# brushed_controller.net
KiCad netlist of a schematic drawn in EAGLE
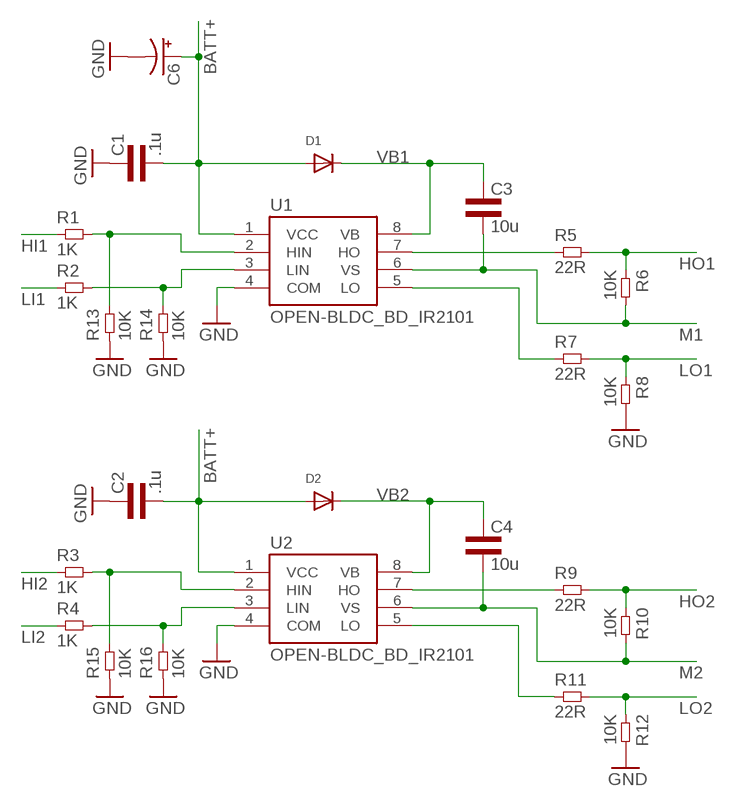
[diagram p0: schematic, sheet 1]
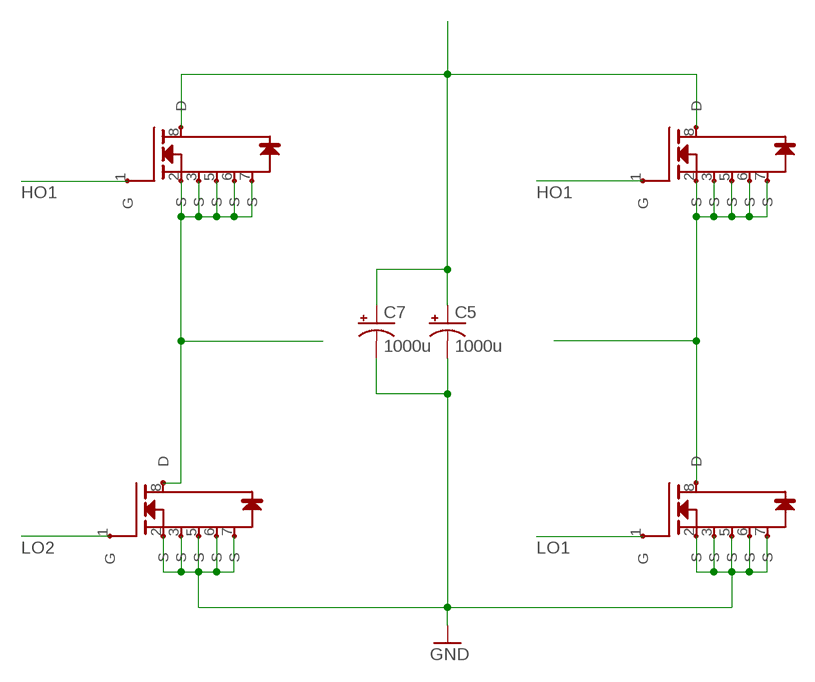
[diagram p1: schematic, sheet 2]

(export (version "E")
  (design (tool "Eeschema 10.0.6"))
  (components
    (comp (ref "C5")
      (value "1000u")
      (footprint "eagle-import:E5-13")
      (libsource (lib "eagle-import") (part "CPOL-USE5-13"))
    )
    (comp (ref "C7")
      (value "1000u")
      (footprint "eagle-import:E5-13")
      (libsource (lib "eagle-import") (part "CPOL-USE5-13"))
    )
    (comp (ref "U$1")
      (value "IR-MOSFETS_IRF3805STRL-7PP")
      (footprint "eagle-import:IR-MOSFETS_D2PAK-7")
      (libsource (lib "eagle-import") (part "IR-MOSFETS_IRF3805STRL-7PP"))
    )
    (comp (ref "U$2")
      (value "IR-MOSFETS_IRF3805STRL-7PP")
      (footprint "eagle-import:IR-MOSFETS_D2PAK-7")
      (libsource (lib "eagle-import") (part "IR-MOSFETS_IRF3805STRL-7PP"))
    )
    (comp (ref "U$3")
      (value "IR-MOSFETS_IRF3805STRL-7PP")
      (footprint "eagle-import:IR-MOSFETS_D2PAK-7")
      (libsource (lib "eagle-import") (part "IR-MOSFETS_IRF3805STRL-7PP"))
    )
    (comp (ref "U$4")
      (value "IR-MOSFETS_IRF3805STRL-7PP")
      (footprint "eagle-import:IR-MOSFETS_D2PAK-7")
      (libsource (lib "eagle-import") (part "IR-MOSFETS_IRF3805STRL-7PP"))
    )
    (comp (ref "C1")
      (value ".1u")
      (footprint "eagle-import:0603L3")
      (libsource (lib "eagle-import") (part "CAP0603L3"))
    )
    (comp (ref "C2")
      (value ".1u")
      (footprint "eagle-import:0603L3")
      (libsource (lib "eagle-import") (part "CAP0603L3"))
    )
    (comp (ref "C3")
      (value "10u")
      (footprint "eagle-import:0805L3")
      (libsource (lib "eagle-import") (part "CAP0805L3"))
    )
    (comp (ref "C4")
      (value "10u")
      (footprint "eagle-import:0805L3")
      (libsource (lib "eagle-import") (part "CAP0805L3"))
    )
    (comp (ref "C6")
      (value "CPOL-USCT7343")
      (footprint "eagle-import:CT7343")
      (libsource (lib "eagle-import") (part "CPOL-USCT7343"))
    )
    (comp (ref "D1")
      (value "DIODESOD-523")
      (footprint "eagle-import:SOD-523")
      (libsource (lib "eagle-import") (part "DIODESOD-523"))
    )
    (comp (ref "D2")
      (value "DIODESOD-523")
      (footprint "eagle-import:SOD-523")
      (libsource (lib "eagle-import") (part "DIODESOD-523"))
    )
    (comp (ref "R1")
      (value "1K")
      (footprint "eagle-import:0603L3")
      (libsource (lib "eagle-import") (part "RES0603L3"))
    )
    (comp (ref "R2")
      (value "1K")
      (footprint "eagle-import:0603L3")
      (libsource (lib "eagle-import") (part "RES0603L3"))
    )
    (comp (ref "R3")
      (value "1K")
      (footprint "eagle-import:0603L3")
      (libsource (lib "eagle-import") (part "RES0603L3"))
    )
    (comp (ref "R4")
      (value "1K")
      (footprint "eagle-import:0603L3")
      (libsource (lib "eagle-import") (part "RES0603L3"))
    )
    (comp (ref "R5")
      (value "22R")
      (footprint "eagle-import:0805L3")
      (libsource (lib "eagle-import") (part "RES0805L3"))
    )
    (comp (ref "R6")
      (value "10K")
      (footprint "eagle-import:0805L3")
      (libsource (lib "eagle-import") (part "RES0805L3"))
    )
    (comp (ref "R7")
      (value "22R")
      (footprint "eagle-import:0805L3")
      (libsource (lib "eagle-import") (part "RES0805L3"))
    )
    (comp (ref "R8")
      (value "10K")
      (footprint "eagle-import:0805L3")
      (libsource (lib "eagle-import") (part "RES0805L3"))
    )
    (comp (ref "R9")
      (value "22R")
      (footprint "eagle-import:0805L3")
      (libsource (lib "eagle-import") (part "RES0805L3"))
    )
    (comp (ref "R10")
      (value "10K")
      (footprint "eagle-import:0805L3")
      (libsource (lib "eagle-import") (part "RES0805L3"))
    )
    (comp (ref "R11")
      (value "22R")
      (footprint "eagle-import:0805L3")
      (libsource (lib "eagle-import") (part "RES0805L3"))
    )
    (comp (ref "R12")
      (value "10K")
      (footprint "eagle-import:0805L3")
      (libsource (lib "eagle-import") (part "RES0805L3"))
    )
    (comp (ref "R13")
      (value "10K")
      (footprint "eagle-import:0603L3")
      (libsource (lib "eagle-import") (part "RES0603L3"))
    )
    (comp (ref "R14")
      (value "10K")
      (footprint "eagle-import:0603L3")
      (libsource (lib "eagle-import") (part "RES0603L3"))
    )
    (comp (ref "R15")
      (value "10K")
      (footprint "eagle-import:0603L3")
      (libsource (lib "eagle-import") (part "RES0603L3"))
    )
    (comp (ref "R16")
      (value "10K")
      (footprint "eagle-import:0603L3")
      (libsource (lib "eagle-import") (part "RES0603L3"))
    )
    (comp (ref "U1")
      (value "OPEN-BLDC_BD_IR2101")
      (footprint "eagle-import:OPEN-BLDC_SO8")
      (libsource (lib "eagle-import") (part "OPEN-BLDC_BD_IR2101"))
    )
    (comp (ref "U2")
      (value "OPEN-BLDC_BD_IR2101")
      (footprint "eagle-import:OPEN-BLDC_SO8")
      (libsource (lib "eagle-import") (part "OPEN-BLDC_BD_IR2101"))
    )
  )
  (nets
    (net (code "1") (name "BATT+") (class "Default")
      (node (ref "C1") (pin "P$2") (pinfunction "2_P$2") (pintype "bidirectional"))
      (node (ref "C2") (pin "P$2") (pinfunction "2_P$2") (pintype "bidirectional"))
      (node (ref "C5") (pin "+") (pinfunction "+_+") (pintype "passive"))
      (node (ref "C6") (pin "+") (pinfunction "+_+") (pintype "passive"))
      (node (ref "C7") (pin "+") (pinfunction "+_+") (pintype "passive"))
      (node (ref "D1") (pin "A") (pinfunction "A_A") (pintype "passive"))
      (node (ref "D2") (pin "A") (pinfunction "A_A") (pintype "passive"))
      (node (ref "U$1") (pin "8") (pinfunction "D_8") (pintype "bidirectional"))
      (node (ref "U$3") (pin "8") (pinfunction "D_8") (pintype "bidirectional"))
      (node (ref "U1") (pin "1") (pinfunction "VCC_1") (pintype "bidirectional"))
      (node (ref "U2") (pin "1") (pinfunction "VCC_1") (pintype "bidirectional"))
    )
    (net (code "2") (name "GND") (class "Default")
      (node (ref "C1") (pin "P$1") (pinfunction "1_P$1") (pintype "bidirectional"))
      (node (ref "C2") (pin "P$1") (pinfunction "1_P$1") (pintype "bidirectional"))
      (node (ref "C5") (pin "-") (pinfunction "-_-") (pintype "passive"))
      (node (ref "C6") (pin "-") (pinfunction "-_-") (pintype "passive"))
      (node (ref "C7") (pin "-") (pinfunction "-_-") (pintype "passive"))
      (node (ref "R12") (pin "2") (pinfunction "2_2") (pintype "bidirectional"))
      (node (ref "R13") (pin "P$1") (pinfunction "1_P$1") (pintype "bidirectional"))
      (node (ref "R14") (pin "P$1") (pinfunction "1_P$1") (pintype "bidirectional"))
      (node (ref "R15") (pin "P$1") (pinfunction "1_P$1") (pintype "bidirectional"))
      (node (ref "R16") (pin "P$1") (pinfunction "1_P$1") (pintype "bidirectional"))
      (node (ref "R8") (pin "2") (pinfunction "2_2") (pintype "bidirectional"))
      (node (ref "U$2") (pin "2") (pinfunction "S_2") (pintype "bidirectional"))
      (node (ref "U$2") (pin "3") (pinfunction "S_3") (pintype "bidirectional"))
      (node (ref "U$2") (pin "5") (pinfunction "S_5") (pintype "bidirectional"))
      (node (ref "U$2") (pin "6") (pinfunction "S_6") (pintype "bidirectional"))
      (node (ref "U$2") (pin "7") (pinfunction "S_7") (pintype "bidirectional"))
      (node (ref "U$4") (pin "2") (pinfunction "S_2") (pintype "bidirectional"))
      (node (ref "U$4") (pin "3") (pinfunction "S_3") (pintype "bidirectional"))
      (node (ref "U$4") (pin "5") (pinfunction "S_5") (pintype "bidirectional"))
      (node (ref "U$4") (pin "6") (pinfunction "S_6") (pintype "bidirectional"))
      (node (ref "U$4") (pin "7") (pinfunction "S_7") (pintype "bidirectional"))
      (node (ref "U1") (pin "4") (pinfunction "COM_4") (pintype "bidirectional"))
      (node (ref "U2") (pin "4") (pinfunction "COM_4") (pintype "bidirectional"))
    )
    (net (code "3") (name "HI1") (class "Default")
      (node (ref "R1") (pin "P$1") (pinfunction "1_P$1") (pintype "bidirectional"))
    )
    (net (code "4") (name "HI2") (class "Default")
      (node (ref "R3") (pin "P$1") (pinfunction "1_P$1") (pintype "bidirectional"))
    )
    (net (code "5") (name "HO1") (class "Default")
      (node (ref "R5") (pin "2") (pinfunction "2_2") (pintype "bidirectional"))
      (node (ref "R6") (pin "1") (pinfunction "1_1") (pintype "bidirectional"))
      (node (ref "U$1") (pin "1") (pinfunction "G_1") (pintype "bidirectional"))
      (node (ref "U$3") (pin "1") (pinfunction "G_1") (pintype "bidirectional"))
    )
    (net (code "6") (name "HO2") (class "Default")
      (node (ref "R10") (pin "1") (pinfunction "1_1") (pintype "bidirectional"))
      (node (ref "R9") (pin "2") (pinfunction "2_2") (pintype "bidirectional"))
    )
    (net (code "7") (name "LI1") (class "Default")
      (node (ref "R2") (pin "P$1") (pinfunction "1_P$1") (pintype "bidirectional"))
    )
    (net (code "8") (name "LI2") (class "Default")
      (node (ref "R4") (pin "P$1") (pinfunction "1_P$1") (pintype "bidirectional"))
    )
    (net (code "9") (name "LO1") (class "Default")
      (node (ref "R7") (pin "2") (pinfunction "2_2") (pintype "bidirectional"))
      (node (ref "R8") (pin "1") (pinfunction "1_1") (pintype "bidirectional"))
      (node (ref "U$4") (pin "1") (pinfunction "G_1") (pintype "bidirectional"))
    )
    (net (code "10") (name "LO2") (class "Default")
      (node (ref "R11") (pin "2") (pinfunction "2_2") (pintype "bidirectional"))
      (node (ref "R12") (pin "1") (pinfunction "1_1") (pintype "bidirectional"))
      (node (ref "U$2") (pin "1") (pinfunction "G_1") (pintype "bidirectional"))
    )
    (net (code "11") (name "M1") (class "Default")
      (node (ref "C3") (pin "2") (pinfunction "2_2") (pintype "bidirectional"))
      (node (ref "R6") (pin "2") (pinfunction "2_2") (pintype "bidirectional"))
      (node (ref "U$1") (pin "2") (pinfunction "S_2") (pintype "bidirectional"))
      (node (ref "U$1") (pin "3") (pinfunction "S_3") (pintype "bidirectional"))
      (node (ref "U$1") (pin "5") (pinfunction "S_5") (pintype "bidirectional"))
      (node (ref "U$1") (pin "6") (pinfunction "S_6") (pintype "bidirectional"))
      (node (ref "U$1") (pin "7") (pinfunction "S_7") (pintype "bidirectional"))
      (node (ref "U$2") (pin "8") (pinfunction "D_8") (pintype "bidirectional"))
      (node (ref "U1") (pin "6") (pinfunction "VS_6") (pintype "bidirectional"))
    )
    (net (code "12") (name "M2") (class "Default")
      (node (ref "C4") (pin "2") (pinfunction "2_2") (pintype "bidirectional"))
      (node (ref "R10") (pin "2") (pinfunction "2_2") (pintype "bidirectional"))
      (node (ref "U$3") (pin "2") (pinfunction "S_2") (pintype "bidirectional"))
      (node (ref "U$3") (pin "3") (pinfunction "S_3") (pintype "bidirectional"))
      (node (ref "U$3") (pin "5") (pinfunction "S_5") (pintype "bidirectional"))
      (node (ref "U$3") (pin "6") (pinfunction "S_6") (pintype "bidirectional"))
      (node (ref "U$3") (pin "7") (pinfunction "S_7") (pintype "bidirectional"))
      (node (ref "U$4") (pin "8") (pinfunction "D_8") (pintype "bidirectional"))
      (node (ref "U2") (pin "6") (pinfunction "VS_6") (pintype "bidirectional"))
    )
    (net (code "13") (name "Net-(R1-2)") (class "Default")
      (node (ref "R1") (pin "P$2") (pinfunction "2_P$2") (pintype "bidirectional"))
      (node (ref "R13") (pin "P$2") (pinfunction "2_P$2") (pintype "bidirectional"))
      (node (ref "U1") (pin "2") (pinfunction "HIN_2") (pintype "bidirectional"))
    )
    (net (code "14") (name "Net-(R14-2)") (class "Default")
      (node (ref "R14") (pin "P$2") (pinfunction "2_P$2") (pintype "bidirectional"))
      (node (ref "R2") (pin "P$2") (pinfunction "2_P$2") (pintype "bidirectional"))
      (node (ref "U1") (pin "3") (pinfunction "LIN_3") (pintype "bidirectional"))
    )
    (net (code "15") (name "Net-(R15-2)") (class "Default")
      (node (ref "R15") (pin "P$2") (pinfunction "2_P$2") (pintype "bidirectional"))
      (node (ref "R3") (pin "P$2") (pinfunction "2_P$2") (pintype "bidirectional"))
      (node (ref "U2") (pin "2") (pinfunction "HIN_2") (pintype "bidirectional"))
    )
    (net (code "16") (name "Net-(R16-2)") (class "Default")
      (node (ref "R16") (pin "P$2") (pinfunction "2_P$2") (pintype "bidirectional"))
      (node (ref "R4") (pin "P$2") (pinfunction "2_P$2") (pintype "bidirectional"))
      (node (ref "U2") (pin "3") (pinfunction "LIN_3") (pintype "bidirectional"))
    )
    (net (code "17") (name "Net-(U1-HO)") (class "Default")
      (node (ref "R5") (pin "1") (pinfunction "1_1") (pintype "bidirectional"))
      (node (ref "U1") (pin "7") (pinfunction "HO_7") (pintype "bidirectional"))
    )
    (net (code "18") (name "Net-(U1-LO)") (class "Default")
      (node (ref "R7") (pin "1") (pinfunction "1_1") (pintype "bidirectional"))
      (node (ref "U1") (pin "5") (pinfunction "LO_5") (pintype "bidirectional"))
    )
    (net (code "19") (name "Net-(U2-HO)") (class "Default")
      (node (ref "R9") (pin "1") (pinfunction "1_1") (pintype "bidirectional"))
      (node (ref "U2") (pin "7") (pinfunction "HO_7") (pintype "bidirectional"))
    )
    (net (code "20") (name "Net-(U2-LO)") (class "Default")
      (node (ref "R11") (pin "1") (pinfunction "1_1") (pintype "bidirectional"))
      (node (ref "U2") (pin "5") (pinfunction "LO_5") (pintype "bidirectional"))
    )
    (net (code "21") (name "VB1") (class "Default")
      (node (ref "C3") (pin "1") (pinfunction "1_1") (pintype "bidirectional"))
      (node (ref "D1") (pin "K") (pinfunction "C_K") (pintype "passive"))
      (node (ref "U1") (pin "8") (pinfunction "VB_8") (pintype "bidirectional"))
    )
    (net (code "22") (name "VB2") (class "Default")
      (node (ref "C4") (pin "1") (pinfunction "1_1") (pintype "bidirectional"))
      (node (ref "D2") (pin "K") (pinfunction "C_K") (pintype "passive"))
      (node (ref "U2") (pin "8") (pinfunction "VB_8") (pintype "bidirectional"))
    )
  )
)
